# wavplayer-v4.net
KiCad netlist of a schematic drawn in EAGLE
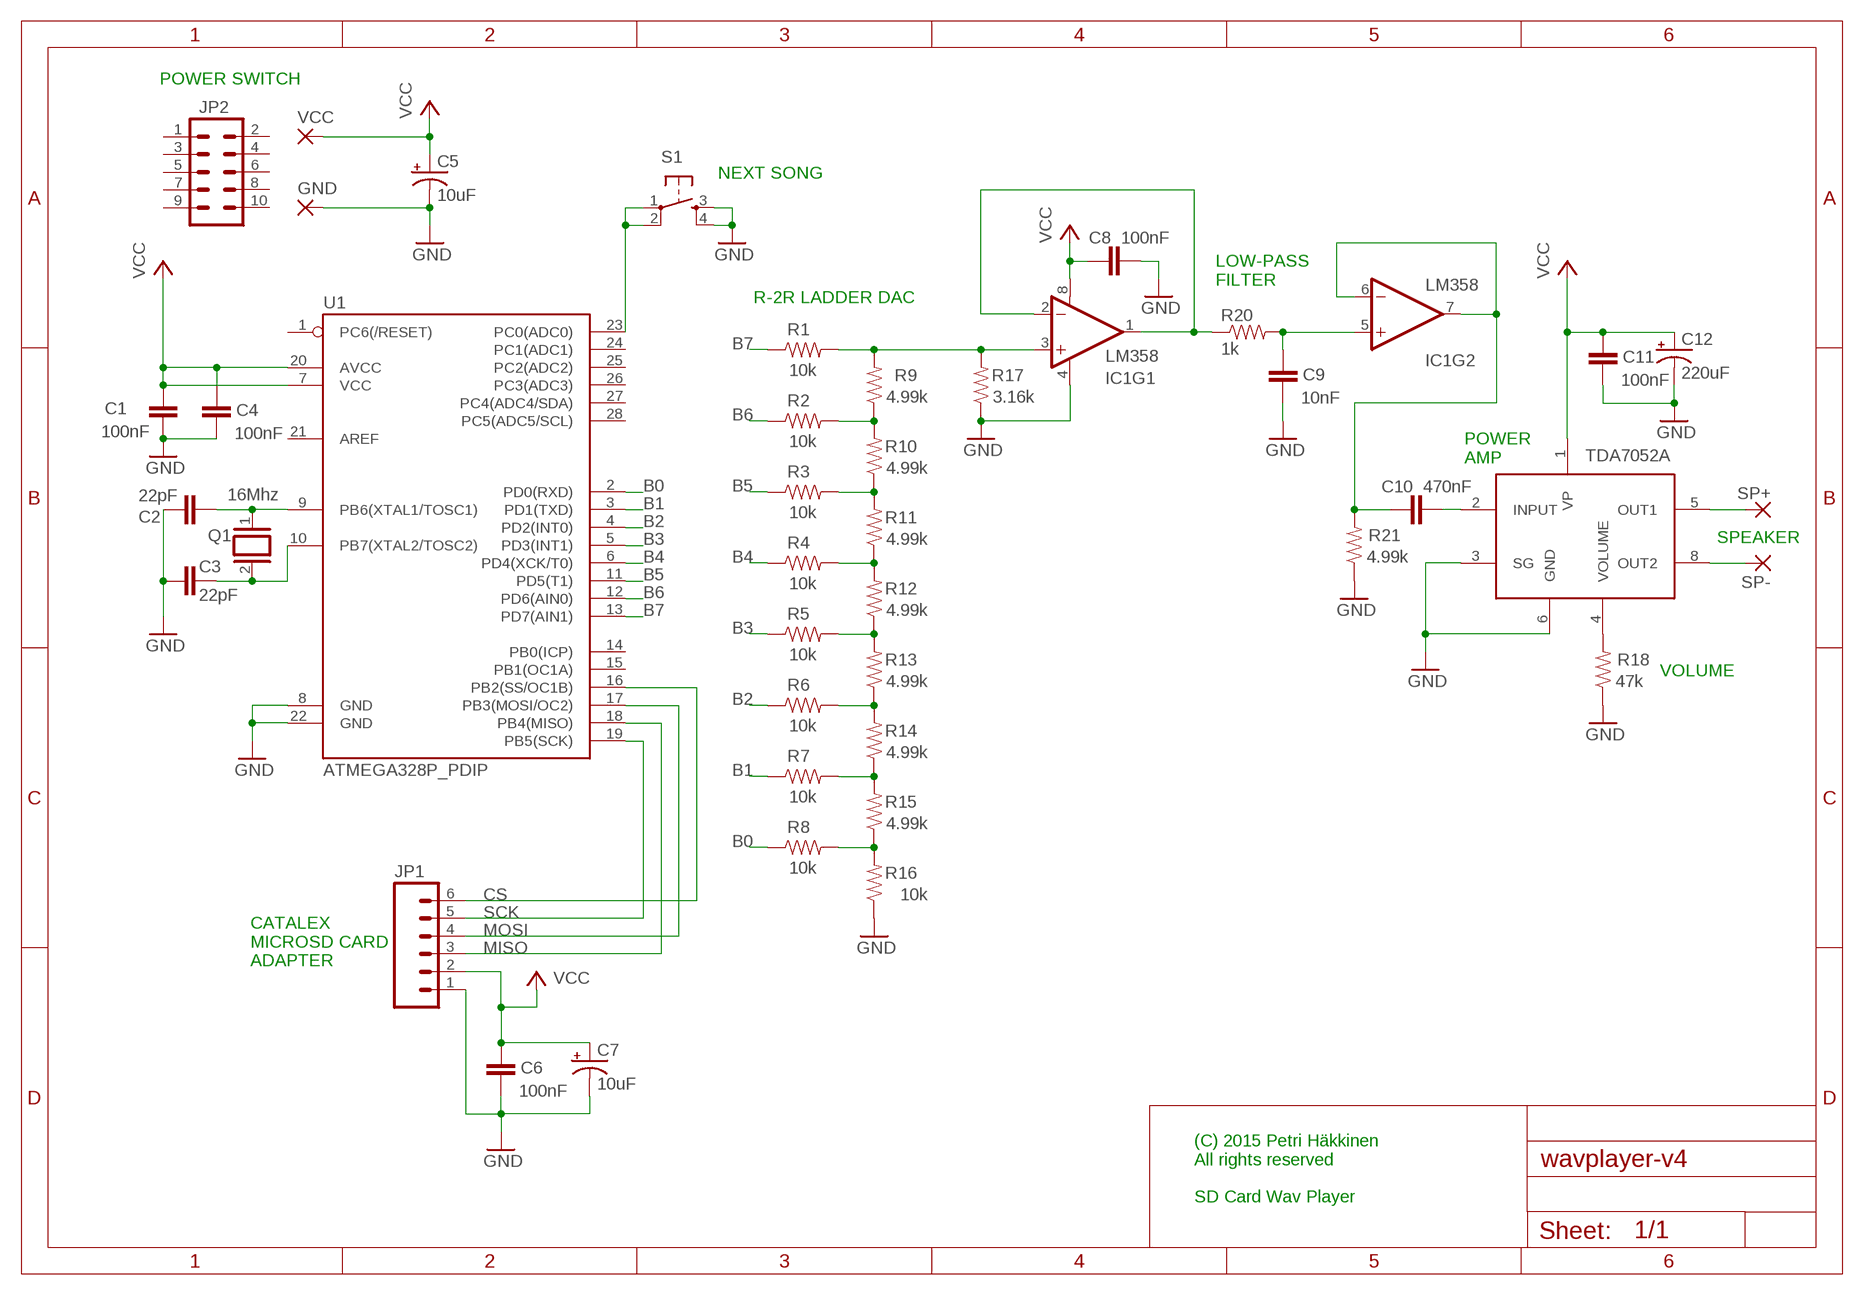
[diagram p0: schematic, sheet 1]

(export (version "E")
  (design (tool "Eeschema 10.0.6"))
  (components
    (comp (ref "C1")
      (value "100nF")
      (footprint "eagle-import:CAP-PTH-SMALL")
      (libsource (lib "eagle-import") (part "CAPPTH"))
    )
    (comp (ref "C2")
      (value "22pF")
      (footprint "eagle-import:CAP-PTH-SMALL")
      (libsource (lib "eagle-import") (part "CAPPTH"))
    )
    (comp (ref "C3")
      (value "22pF")
      (footprint "eagle-import:CAP-PTH-SMALL")
      (libsource (lib "eagle-import") (part "CAPPTH"))
    )
    (comp (ref "C4")
      (value "100nF")
      (footprint "eagle-import:CAP-PTH-SMALL")
      (libsource (lib "eagle-import") (part "CAPPTH"))
    )
    (comp (ref "C5")
      (value "10uF")
      (footprint "eagle-import:CPOL-RADIAL-100UF-25V")
      (libsource (lib "eagle-import") (part "CAP_POLPTH1"))
    )
    (comp (ref "C6")
      (value "100nF")
      (footprint "eagle-import:CAP-PTH-SMALL")
      (libsource (lib "eagle-import") (part "CAPPTH"))
    )
    (comp (ref "C7")
      (value "10uF")
      (footprint "eagle-import:CPOL-RADIAL-100UF-25V")
      (libsource (lib "eagle-import") (part "CAP_POLPTH1"))
    )
    (comp (ref "C8")
      (value "100nF")
      (footprint "eagle-import:CAP-PTH-SMALL")
      (libsource (lib "eagle-import") (part "CAPPTH"))
    )
    (comp (ref "C9")
      (value "10nF")
      (footprint "eagle-import:CAP-PTH-SMALL")
      (libsource (lib "eagle-import") (part "CAPPTH"))
    )
    (comp (ref "C10")
      (value "470nF")
      (footprint "eagle-import:CAP-PTH-SMALL")
      (libsource (lib "eagle-import") (part "CAPPTH"))
    )
    (comp (ref "C11")
      (value "100nF")
      (footprint "eagle-import:CAP-PTH-SMALL")
      (libsource (lib "eagle-import") (part "CAPPTH"))
    )
    (comp (ref "C12")
      (value "220uF")
      (footprint "eagle-import:CPOL-RADIAL-100UF-25V")
      (libsource (lib "eagle-import") (part "CAP_POLPTH1"))
    )
    (comp (ref "GND")
      (value "WIREPAD2,15/1,0")
      (footprint "eagle-import:2,15_1,0")
      (libsource (lib "eagle-import") (part "WIREPAD2,15/1,0"))
    )
    (comp (ref "IC1")
      (value "LM358")
      (footprint "eagle-import:DIP08")
      (libsource (lib "eagle-import") (part "LM358"))
    )
    (comp (ref "JP1")
      (value "M06LONGPADS")
      (footprint "eagle-import:1X06_LONGPADS")
      (libsource (lib "eagle-import") (part "M06LONGPADS"))
    )
    (comp (ref "JP2")
      (value "M05X2NO_SILK")
      (footprint "eagle-import:2X5_NOSILK")
      (libsource (lib "eagle-import") (part "M05X2NO_SILK"))
    )
    (comp (ref "Q1")
      (value "16Mhz")
      (footprint "eagle-import:QS")
      (libsource (lib "eagle-import") (part "XTAL/S"))
    )
    (comp (ref "R1")
      (value "10k")
      (footprint "eagle-import:AXIAL-0.4")
      (libsource (lib "eagle-import") (part "RESISTORPTH-1/4W"))
    )
    (comp (ref "R2")
      (value "10k")
      (footprint "eagle-import:AXIAL-0.4")
      (libsource (lib "eagle-import") (part "RESISTORPTH-1/4W"))
    )
    (comp (ref "R3")
      (value "10k")
      (footprint "eagle-import:AXIAL-0.4")
      (libsource (lib "eagle-import") (part "RESISTORPTH-1/4W"))
    )
    (comp (ref "R4")
      (value "10k")
      (footprint "eagle-import:AXIAL-0.4")
      (libsource (lib "eagle-import") (part "RESISTORPTH-1/4W"))
    )
    (comp (ref "R5")
      (value "10k")
      (footprint "eagle-import:AXIAL-0.4")
      (libsource (lib "eagle-import") (part "RESISTORPTH-1/4W"))
    )
    (comp (ref "R6")
      (value "10k")
      (footprint "eagle-import:AXIAL-0.4")
      (libsource (lib "eagle-import") (part "RESISTORPTH-1/4W"))
    )
    (comp (ref "R7")
      (value "10k")
      (footprint "eagle-import:AXIAL-0.4")
      (libsource (lib "eagle-import") (part "RESISTORPTH-1/4W"))
    )
    (comp (ref "R8")
      (value "10k")
      (footprint "eagle-import:AXIAL-0.4")
      (libsource (lib "eagle-import") (part "RESISTORPTH-1/4W"))
    )
    (comp (ref "R9")
      (value "4.99k")
      (footprint "eagle-import:AXIAL-0.4")
      (libsource (lib "eagle-import") (part "RESISTORPTH-1/4W"))
    )
    (comp (ref "R10")
      (value "4.99k")
      (footprint "eagle-import:AXIAL-0.4")
      (libsource (lib "eagle-import") (part "RESISTORPTH-1/4W"))
    )
    (comp (ref "R11")
      (value "4.99k")
      (footprint "eagle-import:AXIAL-0.4")
      (libsource (lib "eagle-import") (part "RESISTORPTH-1/4W"))
    )
    (comp (ref "R12")
      (value "4.99k")
      (footprint "eagle-import:AXIAL-0.4")
      (libsource (lib "eagle-import") (part "RESISTORPTH-1/4W"))
    )
    (comp (ref "R13")
      (value "4.99k")
      (footprint "eagle-import:AXIAL-0.4")
      (libsource (lib "eagle-import") (part "RESISTORPTH-1/4W"))
    )
    (comp (ref "R14")
      (value "4.99k")
      (footprint "eagle-import:AXIAL-0.4")
      (libsource (lib "eagle-import") (part "RESISTORPTH-1/4W"))
    )
    (comp (ref "R15")
      (value "4.99k")
      (footprint "eagle-import:AXIAL-0.4")
      (libsource (lib "eagle-import") (part "RESISTORPTH-1/4W"))
    )
    (comp (ref "R16")
      (value "10k")
      (footprint "eagle-import:AXIAL-0.4")
      (libsource (lib "eagle-import") (part "RESISTORPTH-1/4W"))
    )
    (comp (ref "R17")
      (value "3.16k")
      (footprint "eagle-import:AXIAL-0.4")
      (libsource (lib "eagle-import") (part "RESISTORPTH-1/4W"))
    )
    (comp (ref "R18")
      (value "47k")
      (footprint "eagle-import:AXIAL-0.1")
      (libsource (lib "eagle-import") (part "RESISTORPTH-1/4W-VERT"))
    )
    (comp (ref "R20")
      (value "1k")
      (footprint "eagle-import:AXIAL-0.4")
      (libsource (lib "eagle-import") (part "RESISTORPTH-1/4W"))
    )
    (comp (ref "R21")
      (value "4.99k")
      (footprint "eagle-import:AXIAL-0.4")
      (libsource (lib "eagle-import") (part "RESISTORPTH-1/4W"))
    )
    (comp (ref "S1")
      (value "TAC_SWITCHPTH")
      (footprint "eagle-import:TACTILE-PTH")
      (libsource (lib "eagle-import") (part "TAC_SWITCHPTH"))
    )
    (comp (ref "SP+")
      (value "WIREPAD2,15/1,0")
      (footprint "eagle-import:2,15_1,0")
      (libsource (lib "eagle-import") (part "WIREPAD2,15/1,0"))
    )
    (comp (ref "SP-")
      (value "WIREPAD2,15/1,0")
      (footprint "eagle-import:2,15_1,0")
      (libsource (lib "eagle-import") (part "WIREPAD2,15/1,0"))
    )
    (comp (ref "U$1")
      (value "TDA7052B")
      (footprint "eagle-import:DIL08")
      (libsource (lib "eagle-import") (part "TDA7052B"))
    )
    (comp (ref "U1")
      (value "ATMEGA328P_PDIP")
      (footprint "eagle-import:DIL28-3")
      (libsource (lib "eagle-import") (part "ATMEGA328P_PDIP"))
    )
    (comp (ref "VCC")
      (value "WIREPAD2,15/1,0")
      (footprint "eagle-import:2,15_1,0")
      (libsource (lib "eagle-import") (part "WIREPAD2,15/1,0"))
    )
  )
  (nets
    (net (code "1") (name "/B0") (class "Default")
      (node (ref "R8") (pin "P$1") (pinfunction "1_P$1") (pintype "passive"))
      (node (ref "U1") (pin "2") (pinfunction "PD0(RXD)_2") (pintype "bidirectional"))
    )
    (net (code "2") (name "/B1") (class "Default")
      (node (ref "R7") (pin "P$1") (pinfunction "1_P$1") (pintype "passive"))
      (node (ref "U1") (pin "3") (pinfunction "PD1(TXD)_3") (pintype "bidirectional"))
    )
    (net (code "3") (name "/B2") (class "Default")
      (node (ref "R6") (pin "P$1") (pinfunction "1_P$1") (pintype "passive"))
      (node (ref "U1") (pin "4") (pinfunction "PD2(INT0)_4") (pintype "bidirectional"))
    )
    (net (code "4") (name "/B3") (class "Default")
      (node (ref "R5") (pin "P$1") (pinfunction "1_P$1") (pintype "passive"))
      (node (ref "U1") (pin "5") (pinfunction "PD3(INT1)_5") (pintype "bidirectional"))
    )
    (net (code "5") (name "/B4") (class "Default")
      (node (ref "R4") (pin "P$1") (pinfunction "1_P$1") (pintype "passive"))
      (node (ref "U1") (pin "6") (pinfunction "PD4(XCK/T0)_6") (pintype "bidirectional"))
    )
    (net (code "6") (name "/B5") (class "Default")
      (node (ref "R3") (pin "P$1") (pinfunction "1_P$1") (pintype "passive"))
      (node (ref "U1") (pin "11") (pinfunction "PD5(T1)_11") (pintype "bidirectional"))
    )
    (net (code "7") (name "/B6") (class "Default")
      (node (ref "R2") (pin "P$1") (pinfunction "1_P$1") (pintype "passive"))
      (node (ref "U1") (pin "12") (pinfunction "PD6(AIN0)_12") (pintype "bidirectional"))
    )
    (net (code "8") (name "/B7") (class "Default")
      (node (ref "R1") (pin "P$1") (pinfunction "1_P$1") (pintype "passive"))
      (node (ref "U1") (pin "13") (pinfunction "PD7(AIN1)_13") (pintype "bidirectional"))
    )
    (net (code "9") (name "/CS") (class "Default")
      (node (ref "JP1") (pin "6") (pinfunction "6_6") (pintype "passive"))
      (node (ref "U1") (pin "16") (pinfunction "PB2(SS/OC1B)_16") (pintype "bidirectional"))
    )
    (net (code "10") (name "/MISO") (class "Default")
      (node (ref "JP1") (pin "3") (pinfunction "3_3") (pintype "passive"))
      (node (ref "U1") (pin "18") (pinfunction "PB4(MISO)_18") (pintype "bidirectional"))
    )
    (net (code "11") (name "/MOSI") (class "Default")
      (node (ref "JP1") (pin "4") (pinfunction "4_4") (pintype "passive"))
      (node (ref "U1") (pin "17") (pinfunction "PB3(MOSI/OC2)_17") (pintype "bidirectional"))
    )
    (net (code "12") (name "/SCK") (class "Default")
      (node (ref "JP1") (pin "5") (pinfunction "5_5") (pintype "passive"))
      (node (ref "U1") (pin "19") (pinfunction "PB5(SCK)_19") (pintype "bidirectional"))
    )
    (net (code "13") (name "GND") (class "Default")
      (node (ref "C1") (pin "2") (pinfunction "2_2") (pintype "passive"))
      (node (ref "C11") (pin "2") (pinfunction "2_2") (pintype "passive"))
      (node (ref "C12") (pin "2") (pinfunction "-_2") (pintype "passive"))
      (node (ref "C2") (pin "2") (pinfunction "2_2") (pintype "passive"))
      (node (ref "C3") (pin "2") (pinfunction "2_2") (pintype "passive"))
      (node (ref "C4") (pin "2") (pinfunction "2_2") (pintype "passive"))
      (node (ref "C5") (pin "2") (pinfunction "-_2") (pintype "passive"))
      (node (ref "C6") (pin "2") (pinfunction "2_2") (pintype "passive"))
      (node (ref "C7") (pin "2") (pinfunction "-_2") (pintype "passive"))
      (node (ref "C8") (pin "2") (pinfunction "2_2") (pintype "passive"))
      (node (ref "C9") (pin "2") (pinfunction "2_2") (pintype "passive"))
      (node (ref "GND") (pin "1") (pinfunction "P_1") (pintype "passive"))
      (node (ref "IC1") (pin "4") (pinfunction "V-_4") (pintype "power_in"))
      (node (ref "JP1") (pin "1") (pinfunction "1_1") (pintype "passive"))
      (node (ref "R16") (pin "P$1") (pinfunction "1_P$1") (pintype "passive"))
      (node (ref "R17") (pin "P$1") (pinfunction "1_P$1") (pintype "passive"))
      (node (ref "R18") (pin "P$1") (pinfunction "1_P$1") (pintype "passive"))
      (node (ref "R21") (pin "P$1") (pinfunction "1_P$1") (pintype "passive"))
      (node (ref "S1") (pin "3") (pinfunction "3_3") (pintype "passive"))
      (node (ref "S1") (pin "4") (pinfunction "4_4") (pintype "passive"))
      (node (ref "U$1") (pin "3") (pinfunction "SG_3") (pintype "power_in"))
      (node (ref "U$1") (pin "6") (pinfunction "GND_6") (pintype "power_in"))
      (node (ref "U1") (pin "22") (pinfunction "GND_22") (pintype "bidirectional"))
      (node (ref "U1") (pin "8") (pinfunction "GND_8") (pintype "bidirectional"))
    )
    (net (code "14") (name "Net-(IC1A-+IN)") (class "Default")
      (node (ref "IC1") (pin "3") (pinfunction "+IN_3") (pintype "input"))
      (node (ref "R1") (pin "P$2") (pinfunction "2_P$2") (pintype "passive"))
      (node (ref "R17") (pin "P$2") (pinfunction "2_P$2") (pintype "passive"))
      (node (ref "R9") (pin "P$2") (pinfunction "2_P$2") (pintype "passive"))
    )
    (net (code "15") (name "Net-(IC1A--IN)") (class "Default")
      (node (ref "IC1") (pin "1") (pinfunction "OUT_1") (pintype "output"))
      (node (ref "IC1") (pin "2") (pinfunction "-IN_2") (pintype "input"))
      (node (ref "R20") (pin "P$1") (pinfunction "1_P$1") (pintype "passive"))
    )
    (net (code "16") (name "Net-(IC1B-+IN)") (class "Default")
      (node (ref "C9") (pin "1") (pinfunction "1_1") (pintype "passive"))
      (node (ref "IC1") (pin "5") (pinfunction "+IN_5") (pintype "input"))
      (node (ref "R20") (pin "P$2") (pinfunction "2_P$2") (pintype "passive"))
    )
    (net (code "17") (name "Net-(IC1B--IN)") (class "Default")
      (node (ref "C10") (pin "1") (pinfunction "1_1") (pintype "passive"))
      (node (ref "IC1") (pin "6") (pinfunction "-IN_6") (pintype "input"))
      (node (ref "IC1") (pin "7") (pinfunction "OUT_7") (pintype "output"))
      (node (ref "R21") (pin "P$2") (pinfunction "2_P$2") (pintype "passive"))
    )
    (net (code "18") (name "Net-(R10-1)") (class "Default")
      (node (ref "R10") (pin "P$1") (pinfunction "1_P$1") (pintype "passive"))
      (node (ref "R11") (pin "P$2") (pinfunction "2_P$2") (pintype "passive"))
      (node (ref "R3") (pin "P$2") (pinfunction "2_P$2") (pintype "passive"))
    )
    (net (code "19") (name "Net-(R10-2)") (class "Default")
      (node (ref "R10") (pin "P$2") (pinfunction "2_P$2") (pintype "passive"))
      (node (ref "R2") (pin "P$2") (pinfunction "2_P$2") (pintype "passive"))
      (node (ref "R9") (pin "P$1") (pinfunction "1_P$1") (pintype "passive"))
    )
    (net (code "20") (name "Net-(R11-1)") (class "Default")
      (node (ref "R11") (pin "P$1") (pinfunction "1_P$1") (pintype "passive"))
      (node (ref "R12") (pin "P$2") (pinfunction "2_P$2") (pintype "passive"))
      (node (ref "R4") (pin "P$2") (pinfunction "2_P$2") (pintype "passive"))
    )
    (net (code "21") (name "Net-(R12-1)") (class "Default")
      (node (ref "R12") (pin "P$1") (pinfunction "1_P$1") (pintype "passive"))
      (node (ref "R13") (pin "P$2") (pinfunction "2_P$2") (pintype "passive"))
      (node (ref "R5") (pin "P$2") (pinfunction "2_P$2") (pintype "passive"))
    )
    (net (code "22") (name "Net-(R13-1)") (class "Default")
      (node (ref "R13") (pin "P$1") (pinfunction "1_P$1") (pintype "passive"))
      (node (ref "R14") (pin "P$2") (pinfunction "2_P$2") (pintype "passive"))
      (node (ref "R6") (pin "P$2") (pinfunction "2_P$2") (pintype "passive"))
    )
    (net (code "23") (name "Net-(R14-1)") (class "Default")
      (node (ref "R14") (pin "P$1") (pinfunction "1_P$1") (pintype "passive"))
      (node (ref "R15") (pin "P$2") (pinfunction "2_P$2") (pintype "passive"))
      (node (ref "R7") (pin "P$2") (pinfunction "2_P$2") (pintype "passive"))
    )
    (net (code "24") (name "Net-(R15-1)") (class "Default")
      (node (ref "R15") (pin "P$1") (pinfunction "1_P$1") (pintype "passive"))
      (node (ref "R16") (pin "P$2") (pinfunction "2_P$2") (pintype "passive"))
      (node (ref "R8") (pin "P$2") (pinfunction "2_P$2") (pintype "passive"))
    )
    (net (code "25") (name "Net-(R18-2)") (class "Default")
      (node (ref "R18") (pin "P$2") (pinfunction "2_P$2") (pintype "passive"))
      (node (ref "U$1") (pin "4") (pinfunction "VOLUME_4") (pintype "power_in"))
    )
    (net (code "26") (name "Net-(SP+-P)") (class "Default")
      (node (ref "SP+") (pin "1") (pinfunction "P_1") (pintype "passive"))
      (node (ref "U$1") (pin "5") (pinfunction "OUT1_5") (pintype "output"))
    )
    (net (code "27") (name "Net-(SP--P)") (class "Default")
      (node (ref "SP-") (pin "1") (pinfunction "P_1") (pintype "passive"))
      (node (ref "U$1") (pin "8") (pinfunction "OUT2_8") (pintype "output"))
    )
    (net (code "28") (name "Net-(U$1-INPUT)") (class "Default")
      (node (ref "C10") (pin "2") (pinfunction "2_2") (pintype "passive"))
      (node (ref "U$1") (pin "2") (pinfunction "INPUT_2") (pintype "input"))
    )
    (net (code "29") (name "Net-(U1-PB6(XTAL1{slash}TOSC1))") (class "Default")
      (node (ref "C2") (pin "1") (pinfunction "1_1") (pintype "passive"))
      (node (ref "Q1") (pin "1") (pinfunction "1_1") (pintype "passive"))
      (node (ref "U1") (pin "9") (pinfunction "PB6(XTAL1/TOSC1)_9") (pintype "bidirectional"))
    )
    (net (code "30") (name "Net-(U1-PB7(XTAL2{slash}TOSC2))") (class "Default")
      (node (ref "C3") (pin "1") (pinfunction "1_1") (pintype "passive"))
      (node (ref "Q1") (pin "2") (pinfunction "2_2") (pintype "passive"))
      (node (ref "U1") (pin "10") (pinfunction "PB7(XTAL2/TOSC2)_10") (pintype "bidirectional"))
    )
    (net (code "31") (name "Net-(U1-PC0(ADC0))") (class "Default")
      (node (ref "S1") (pin "1") (pinfunction "1_1") (pintype "passive"))
      (node (ref "S1") (pin "2") (pinfunction "2_2") (pintype "passive"))
      (node (ref "U1") (pin "23") (pinfunction "PC0(ADC0)_23") (pintype "bidirectional"))
    )
    (net (code "32") (name "VCC") (class "Default")
      (node (ref "C1") (pin "1") (pinfunction "1_1") (pintype "passive"))
      (node (ref "C11") (pin "1") (pinfunction "1_1") (pintype "passive"))
      (node (ref "C12") (pin "1") (pinfunction "+_1") (pintype "passive"))
      (node (ref "C4") (pin "1") (pinfunction "1_1") (pintype "passive"))
      (node (ref "C5") (pin "1") (pinfunction "+_1") (pintype "passive"))
      (node (ref "C6") (pin "1") (pinfunction "1_1") (pintype "passive"))
      (node (ref "C7") (pin "1") (pinfunction "+_1") (pintype "passive"))
      (node (ref "C8") (pin "1") (pinfunction "1_1") (pintype "passive"))
      (node (ref "IC1") (pin "8") (pinfunction "V+_8") (pintype "power_in"))
      (node (ref "JP1") (pin "2") (pinfunction "2_2") (pintype "passive"))
      (node (ref "U$1") (pin "1") (pinfunction "VP_1") (pintype "power_in"))
      (node (ref "U1") (pin "20") (pinfunction "AVCC_20") (pintype "bidirectional"))
      (node (ref "U1") (pin "7") (pinfunction "VCC_7") (pintype "bidirectional"))
      (node (ref "VCC") (pin "1") (pinfunction "P_1") (pintype "passive"))
    )
    (net (code "33") (name "unconnected-(JP2-Pad1)") (class "Default")
      (node (ref "JP2") (pin "1") (pinfunction "1_1") (pintype "passive"))
    )
    (net (code "34") (name "unconnected-(JP2-Pad2)") (class "Default")
      (node (ref "JP2") (pin "2") (pinfunction "2_2") (pintype "passive"))
    )
    (net (code "35") (name "unconnected-(JP2-Pad3)") (class "Default")
      (node (ref "JP2") (pin "3") (pinfunction "3_3") (pintype "passive"))
    )
    (net (code "36") (name "unconnected-(JP2-Pad4)") (class "Default")
      (node (ref "JP2") (pin "4") (pinfunction "4_4") (pintype "passive"))
    )
    (net (code "37") (name "unconnected-(JP2-Pad5)") (class "Default")
      (node (ref "JP2") (pin "5") (pinfunction "5_5") (pintype "passive"))
    )
    (net (code "38") (name "unconnected-(JP2-Pad6)") (class "Default")
      (node (ref "JP2") (pin "6") (pinfunction "6_6") (pintype "passive"))
    )
    (net (code "39") (name "unconnected-(JP2-Pad7)") (class "Default")
      (node (ref "JP2") (pin "7") (pinfunction "7_7") (pintype "passive"))
    )
    (net (code "40") (name "unconnected-(JP2-Pad8)") (class "Default")
      (node (ref "JP2") (pin "8") (pinfunction "8_8") (pintype "passive"))
    )
    (net (code "41") (name "unconnected-(JP2-Pad9)") (class "Default")
      (node (ref "JP2") (pin "9") (pinfunction "9_9") (pintype "passive"))
    )
    (net (code "42") (name "unconnected-(JP2-Pad10)") (class "Default")
      (node (ref "JP2") (pin "10") (pinfunction "10_10") (pintype "passive"))
    )
    (net (code "43") (name "unconnected-(U1-AREF-Pad21)") (class "Default")
      (node (ref "U1") (pin "21") (pinfunction "AREF_21") (pintype "bidirectional"))
    )
    (net (code "44") (name "unconnected-(U1-PB0(ICP)-Pad14)") (class "Default")
      (node (ref "U1") (pin "14") (pinfunction "PB0(ICP)_14") (pintype "bidirectional"))
    )
    (net (code "45") (name "unconnected-(U1-PB1(OC1A)-Pad15)") (class "Default")
      (node (ref "U1") (pin "15") (pinfunction "PB1(OC1A)_15") (pintype "bidirectional"))
    )
    (net (code "46") (name "unconnected-(U1-PC1(ADC1)-Pad24)") (class "Default")
      (node (ref "U1") (pin "24") (pinfunction "PC1(ADC1)_24") (pintype "bidirectional"))
    )
    (net (code "47") (name "unconnected-(U1-PC2(ADC2)-Pad25)") (class "Default")
      (node (ref "U1") (pin "25") (pinfunction "PC2(ADC2)_25") (pintype "bidirectional"))
    )
    (net (code "48") (name "unconnected-(U1-PC3(ADC3)-Pad26)") (class "Default")
      (node (ref "U1") (pin "26") (pinfunction "PC3(ADC3)_26") (pintype "bidirectional"))
    )
    (net (code "49") (name "unconnected-(U1-PC4(ADC4{slash}SDA)-Pad27)") (class "Default")
      (node (ref "U1") (pin "27") (pinfunction "PC4(ADC4/SDA)_27") (pintype "bidirectional"))
    )
    (net (code "50") (name "unconnected-(U1-PC5(ADC5{slash}SCL)-Pad28)") (class "Default")
      (node (ref "U1") (pin "28") (pinfunction "PC5(ADC5/SCL)_28") (pintype "bidirectional"))
    )
    (net (code "51") (name "unconnected-(U1-PC6({slash}RESET)-Pad1)") (class "Default")
      (node (ref "U1") (pin "1") (pinfunction "PC6(/RESET)_1") (pintype "bidirectional"))
    )
  )
)
